# zxld381-boost-driver-24mm-9leds-mk-1.net
KiCad netlist of a schematic drawn in EAGLE
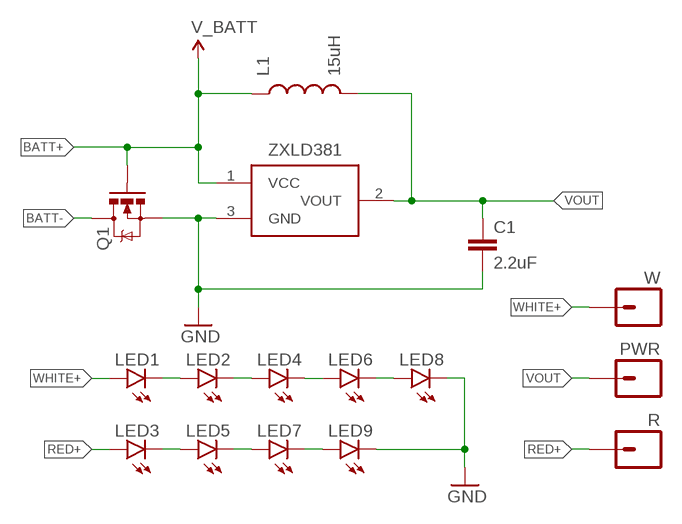
[diagram p0: schematic, sheet 1]

(export (version "E")
  (design (tool "Eeschema 10.0.6"))
  (components
    (comp (ref "C1")
      (value "2.2uF")
      (footprint "eagle-import:C0805")
      (libsource (lib "eagle-import") (part "CAPACITOR-CERAMICC0805"))
    )
    (comp (ref "L1")
      (value "15uH")
      (footprint "eagle-import:L0805")
      (libsource (lib "eagle-import") (part "INDUCTORL0805"))
    )
    (comp (ref "LED1")
      (value "LED5MM_SHORTPADS")
      (footprint "eagle-import:LED5MM_SHORTPADS")
      (libsource (lib "eagle-import") (part "LED5MM_SHORTPADS"))
    )
    (comp (ref "LED2")
      (value "LED5MM_SHORTPADS")
      (footprint "eagle-import:LED5MM_SHORTPADS")
      (libsource (lib "eagle-import") (part "LED5MM_SHORTPADS"))
    )
    (comp (ref "LED3")
      (value "LED5MM_SHORTPADS")
      (footprint "eagle-import:LED5MM_SHORTPADS")
      (libsource (lib "eagle-import") (part "LED5MM_SHORTPADS"))
    )
    (comp (ref "LED4")
      (value "LED5MM_SHORTPADS")
      (footprint "eagle-import:LED5MM_SHORTPADS")
      (libsource (lib "eagle-import") (part "LED5MM_SHORTPADS"))
    )
    (comp (ref "LED5")
      (value "LED5MM_SHORTPADS")
      (footprint "eagle-import:LED5MM_SHORTPADS")
      (libsource (lib "eagle-import") (part "LED5MM_SHORTPADS"))
    )
    (comp (ref "LED6")
      (value "LED5MM_SHORTPADS")
      (footprint "eagle-import:LED5MM_SHORTPADS")
      (libsource (lib "eagle-import") (part "LED5MM_SHORTPADS"))
    )
    (comp (ref "LED7")
      (value "LED5MM_SHORTPADS")
      (footprint "eagle-import:LED5MM_SHORTPADS")
      (libsource (lib "eagle-import") (part "LED5MM_SHORTPADS"))
    )
    (comp (ref "LED8")
      (value "LED5MM_SHORTPADS")
      (footprint "eagle-import:LED5MM_SHORTPADS")
      (libsource (lib "eagle-import") (part "LED5MM_SHORTPADS"))
    )
    (comp (ref "LED9")
      (value "LED5MM_SHORTPADS")
      (footprint "eagle-import:LED5MM_SHORTPADS")
      (libsource (lib "eagle-import") (part "LED5MM_SHORTPADS"))
    )
    (comp (ref "PWR")
      (value "M01PTH-TINY")
      (footprint "eagle-import:1X01_635UM")
      (libsource (lib "eagle-import") (part "M01PTH-TINY"))
    )
    (comp (ref "Q1")
      (value "MOSFET-NCHANNELIRLML2502")
      (footprint "eagle-import:SOT23")
      (libsource (lib "eagle-import") (part "MOSFET-NCHANNELIRLML2502"))
    )
    (comp (ref "R")
      (value "M01PTH-TINY")
      (footprint "eagle-import:1X01_635UM")
      (libsource (lib "eagle-import") (part "M01PTH-TINY"))
    )
    (comp (ref "W")
      (value "M01PTH-TINY")
      (footprint "eagle-import:1X01_635UM")
      (libsource (lib "eagle-import") (part "M01PTH-TINY"))
    )
    (comp (ref "ZXLD381")
      (value "ZXLD381")
      (footprint "eagle-import:SOT23-3")
      (libsource (lib "eagle-import") (part "ZXLD381"))
    )
  )
  (nets
    (net (code "1") (name "BATT+") (class "Default")
      (node (ref "L1") (pin "1") (pinfunction "1_1") (pintype "passive"))
      (node (ref "Q1") (pin "1") (pinfunction "G_1") (pintype "passive"))
      (node (ref "ZXLD381") (pin "1") (pinfunction "VCC_1") (pintype "bidirectional"))
    )
    (net (code "2") (name "BATT-") (class "Default")
      (node (ref "Q1") (pin "3") (pinfunction "D_3") (pintype "passive"))
    )
    (net (code "3") (name "GND") (class "Default")
      (node (ref "C1") (pin "2") (pinfunction "2_2") (pintype "passive"))
      (node (ref "LED8") (pin "K") (pinfunction "C_K") (pintype "passive"))
      (node (ref "LED9") (pin "K") (pinfunction "C_K") (pintype "passive"))
      (node (ref "Q1") (pin "2") (pinfunction "S_2") (pintype "passive"))
      (node (ref "ZXLD381") (pin "3") (pinfunction "GND_3") (pintype "bidirectional"))
    )
    (net (code "4") (name "Net-(LED1-C)") (class "Default")
      (node (ref "LED1") (pin "K") (pinfunction "C_K") (pintype "passive"))
      (node (ref "LED2") (pin "A") (pinfunction "A_A") (pintype "passive"))
    )
    (net (code "5") (name "Net-(LED2-C)") (class "Default")
      (node (ref "LED2") (pin "K") (pinfunction "C_K") (pintype "passive"))
      (node (ref "LED4") (pin "A") (pinfunction "A_A") (pintype "passive"))
    )
    (net (code "6") (name "Net-(LED3-C)") (class "Default")
      (node (ref "LED3") (pin "K") (pinfunction "C_K") (pintype "passive"))
      (node (ref "LED5") (pin "A") (pinfunction "A_A") (pintype "passive"))
    )
    (net (code "7") (name "Net-(LED4-C)") (class "Default")
      (node (ref "LED4") (pin "K") (pinfunction "C_K") (pintype "passive"))
      (node (ref "LED6") (pin "A") (pinfunction "A_A") (pintype "passive"))
    )
    (net (code "8") (name "Net-(LED5-C)") (class "Default")
      (node (ref "LED5") (pin "K") (pinfunction "C_K") (pintype "passive"))
      (node (ref "LED7") (pin "A") (pinfunction "A_A") (pintype "passive"))
    )
    (net (code "9") (name "Net-(LED6-C)") (class "Default")
      (node (ref "LED6") (pin "K") (pinfunction "C_K") (pintype "passive"))
      (node (ref "LED8") (pin "A") (pinfunction "A_A") (pintype "passive"))
    )
    (net (code "10") (name "Net-(LED7-C)") (class "Default")
      (node (ref "LED7") (pin "K") (pinfunction "C_K") (pintype "passive"))
      (node (ref "LED9") (pin "A") (pinfunction "A_A") (pintype "passive"))
    )
    (net (code "11") (name "RED+") (class "Default")
      (node (ref "LED3") (pin "A") (pinfunction "A_A") (pintype "passive"))
      (node (ref "R") (pin "P$1") (pinfunction "1_P$1") (pintype "passive"))
    )
    (net (code "12") (name "VOUT") (class "Default")
      (node (ref "C1") (pin "1") (pinfunction "1_1") (pintype "passive"))
      (node (ref "L1") (pin "2") (pinfunction "2_2") (pintype "passive"))
      (node (ref "PWR") (pin "P$1") (pinfunction "1_P$1") (pintype "passive"))
      (node (ref "ZXLD381") (pin "2") (pinfunction "VOUT_2") (pintype "bidirectional"))
    )
    (net (code "13") (name "WHITE+") (class "Default")
      (node (ref "LED1") (pin "A") (pinfunction "A_A") (pintype "passive"))
      (node (ref "W") (pin "P$1") (pinfunction "1_P$1") (pintype "passive"))
    )
  )
)
